# PPM2DSM_MINI.net
KiCad netlist of a schematic drawn in EAGLE
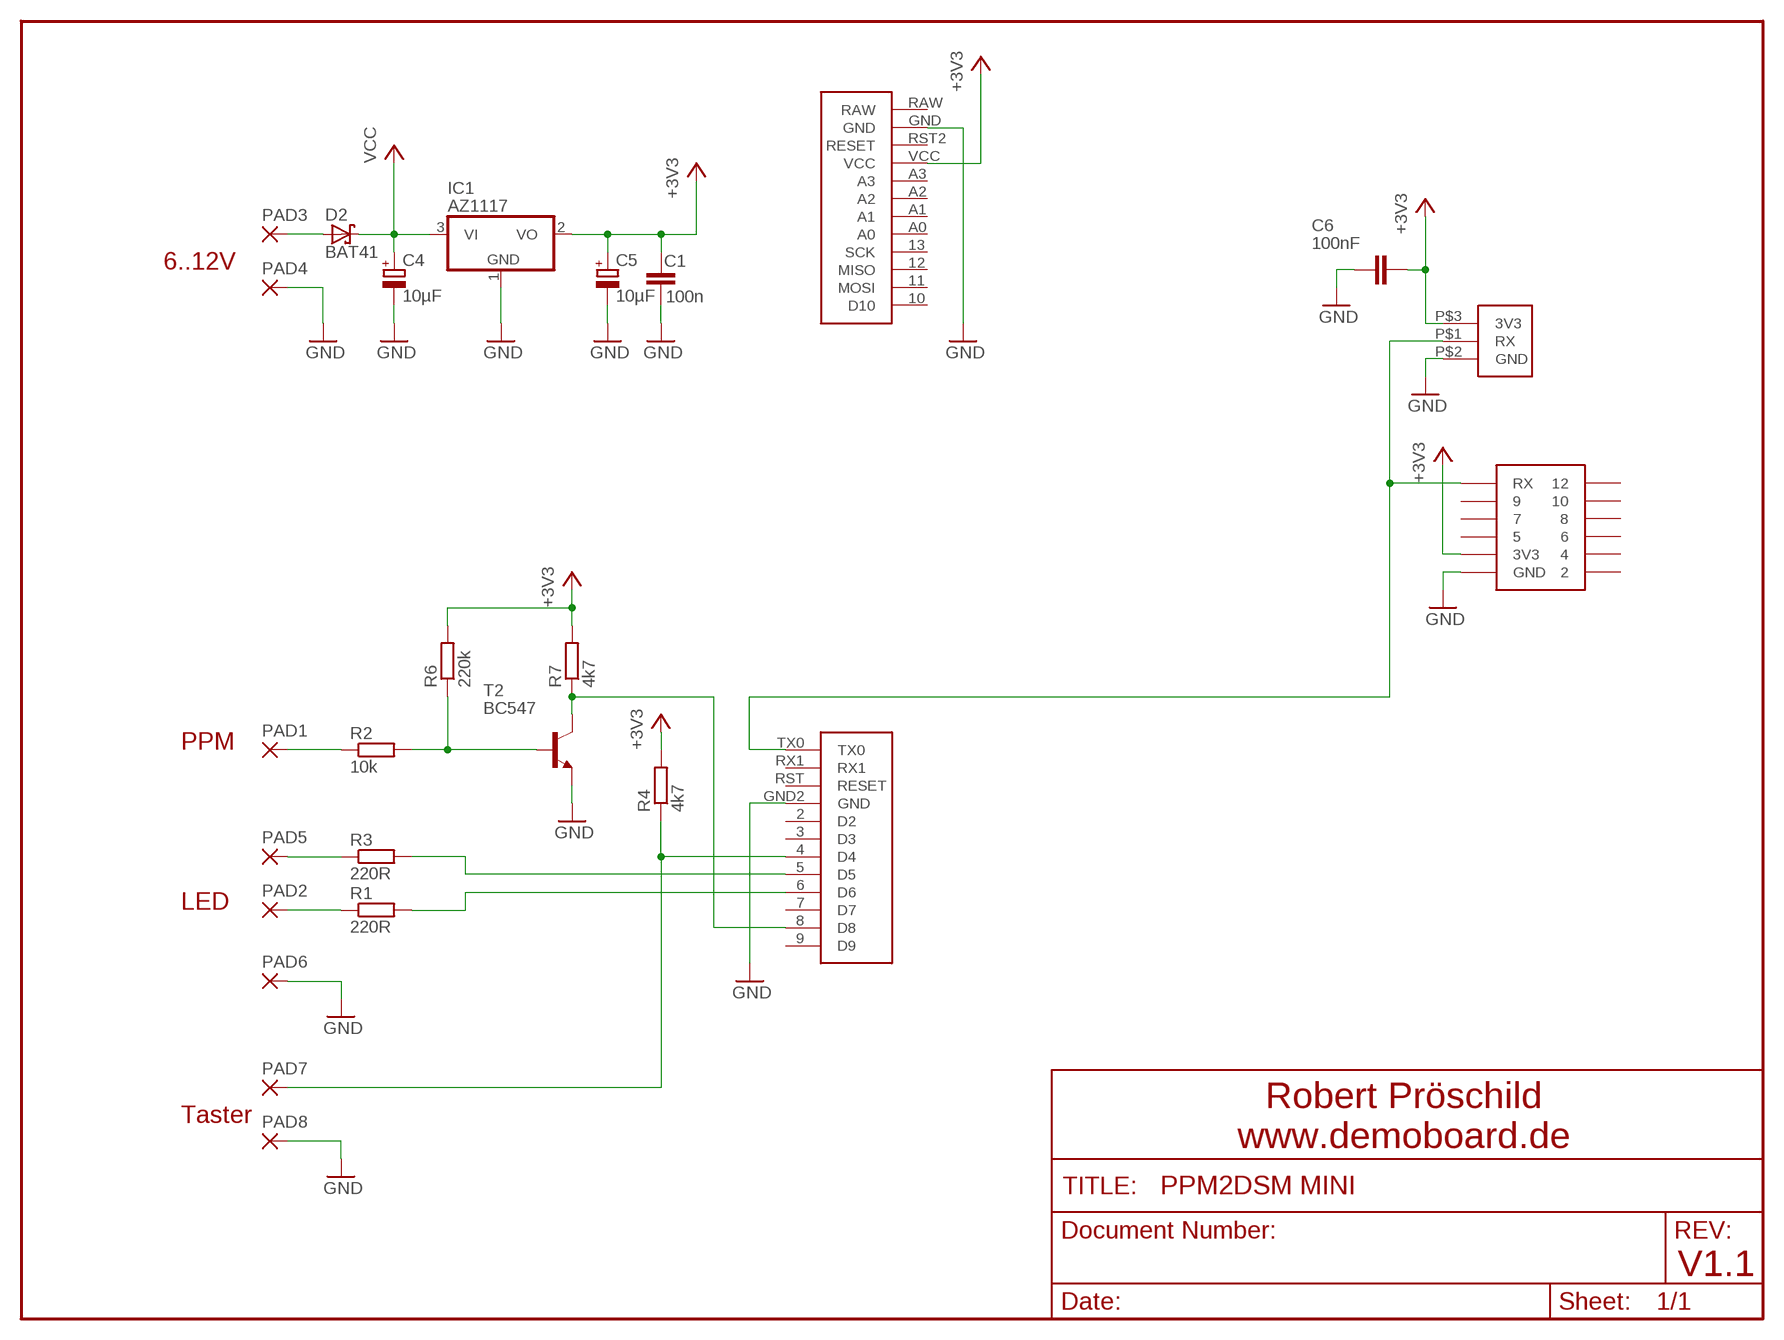
[diagram p0: schematic, sheet 1]

(export (version "E")
  (design (tool "Eeschema 10.0.6"))
  (components
    (comp (ref "C1")
      (value "100n")
      (footprint "eagle-import:C025-024X044")
      (libsource (lib "eagle-import") (part "C-EU025-024X044"))
    )
    (comp (ref "C4")
      (value "10µF")
      (footprint "eagle-import:TT2D4")
      (libsource (lib "eagle-import") (part "CPOL-EUTT2D4"))
    )
    (comp (ref "C5")
      (value "10µF")
      (footprint "eagle-import:TT2D4")
      (libsource (lib "eagle-import") (part "CPOL-EUTT2D4"))
    )
    (comp (ref "C6")
      (value "100nF")
      (footprint "eagle-import:C025-024X044")
      (libsource (lib "eagle-import") (part "C-EU025-024X044"))
    )
    (comp (ref "D2")
      (value "BAT41")
      (footprint "eagle-import:DO35-7")
      (libsource (lib "eagle-import") (part "SCHOTTKY-DIODEDO35-7"))
    )
    (comp (ref "IC1")
      (value "AZ1117")
      (footprint "eagle-import:SOT223")
      (libsource (lib "eagle-import") (part "AZ1117"))
    )
    (comp (ref "IC2")
      (value "X10EMTX")
      (footprint "eagle-import:X10EMTX")
      (libsource (lib "eagle-import") (part "X10EMTX"))
    )
    (comp (ref "IC3")
      (value "MINI_PRO")
      (footprint "eagle-import:PRO-MINI")
      (libsource (lib "eagle-import") (part "MINI_PRO"))
    )
    (comp (ref "IC4")
      (value "X1TX0")
      (footprint "eagle-import:X1TX0")
      (libsource (lib "eagle-import") (part "X1TX0"))
    )
    (comp (ref "PAD1")
      (value "SMD5")
      (footprint "eagle-import:SMD2,54-5,08")
      (libsource (lib "eagle-import") (part "SMD5"))
    )
    (comp (ref "PAD2")
      (value "SMD5")
      (footprint "eagle-import:SMD2,54-5,08")
      (libsource (lib "eagle-import") (part "SMD5"))
    )
    (comp (ref "PAD3")
      (value "SMD5")
      (footprint "eagle-import:SMD2,54-5,08")
      (libsource (lib "eagle-import") (part "SMD5"))
    )
    (comp (ref "PAD4")
      (value "SMD5")
      (footprint "eagle-import:SMD2,54-5,08")
      (libsource (lib "eagle-import") (part "SMD5"))
    )
    (comp (ref "PAD5")
      (value "SMD5")
      (footprint "eagle-import:SMD2,54-5,08")
      (libsource (lib "eagle-import") (part "SMD5"))
    )
    (comp (ref "PAD6")
      (value "SMD5")
      (footprint "eagle-import:SMD2,54-5,08")
      (libsource (lib "eagle-import") (part "SMD5"))
    )
    (comp (ref "PAD7")
      (value "SMD5")
      (footprint "eagle-import:SMD2,54-5,08")
      (libsource (lib "eagle-import") (part "SMD5"))
    )
    (comp (ref "PAD8")
      (value "SMD5")
      (footprint "eagle-import:SMD2,54-5,08")
      (libsource (lib "eagle-import") (part "SMD5"))
    )
    (comp (ref "R1")
      (value "220R")
      (footprint "eagle-import:0204_5")
      (libsource (lib "eagle-import") (part "R-EU_0204/5"))
    )
    (comp (ref "R2")
      (value "10k")
      (footprint "eagle-import:0204_5")
      (libsource (lib "eagle-import") (part "R-EU_0204/5"))
    )
    (comp (ref "R3")
      (value "220R")
      (footprint "eagle-import:0204_5")
      (libsource (lib "eagle-import") (part "R-EU_0204/5"))
    )
    (comp (ref "R4")
      (value "4k7")
      (footprint "eagle-import:0204_5")
      (libsource (lib "eagle-import") (part "R-EU_0204/5"))
    )
    (comp (ref "R6")
      (value "220k")
      (footprint "eagle-import:0204_5")
      (libsource (lib "eagle-import") (part "R-EU_0204/5"))
    )
    (comp (ref "R7")
      (value "4k7")
      (footprint "eagle-import:0204_5")
      (libsource (lib "eagle-import") (part "R-EU_0204/5"))
    )
    (comp (ref "T2")
      (value "BC547")
      (footprint "eagle-import:TO92")
      (libsource (lib "eagle-import") (part "BC547"))
    )
  )
  (nets
    (net (code "1") (name "+3V3") (class "Default")
      (node (ref "C1") (pin "2") (pinfunction "2_2") (pintype "passive"))
      (node (ref "C5") (pin "+") (pinfunction "+_+") (pintype "passive"))
      (node (ref "C6") (pin "2") (pinfunction "2_2") (pintype "passive"))
      (node (ref "IC1") (pin "2") (pinfunction "VO_2") (pintype "passive"))
      (node (ref "IC2") (pin "P$3") (pinfunction "3V3_P$3") (pintype "power_in"))
      (node (ref "IC3") (pin "VCC") (pinfunction "VCC_VCC") (pintype "power_in"))
      (node (ref "IC4") (pin "3") (pinfunction "3V3_3") (pintype "bidirectional"))
      (node (ref "R4") (pin "2") (pinfunction "2_2") (pintype "passive"))
      (node (ref "R6") (pin "2") (pinfunction "2_2") (pintype "passive"))
      (node (ref "R7") (pin "2") (pinfunction "2_2") (pintype "passive"))
    )
    (net (code "2") (name "/2") (class "Default")
      (node (ref "IC4") (pin "2") (pinfunction "2_2") (pintype "power_in"))
    )
    (net (code "3") (name "/4") (class "Default")
      (node (ref "IC4") (pin "4") (pinfunction "4_4") (pintype "power_in"))
    )
    (net (code "4") (name "/RAW") (class "Default")
      (node (ref "IC3") (pin "RAW") (pinfunction "RAW_RAW") (pintype "power_in"))
    )
    (net (code "5") (name "GND") (class "Default")
      (node (ref "C1") (pin "1") (pinfunction "1_1") (pintype "passive"))
      (node (ref "C4") (pin "-") (pinfunction "-_-") (pintype "passive"))
      (node (ref "C5") (pin "-") (pinfunction "-_-") (pintype "passive"))
      (node (ref "C6") (pin "1") (pinfunction "1_1") (pintype "passive"))
      (node (ref "IC1") (pin "1") (pinfunction "GND_1") (pintype "passive"))
      (node (ref "IC2") (pin "P$2") (pinfunction "GND_P$2") (pintype "power_in"))
      (node (ref "IC3") (pin "GND") (pinfunction "GND_GND") (pintype "power_in"))
      (node (ref "IC3") (pin "GND2") (pinfunction "GND_GND2") (pintype "power_in"))
      (node (ref "IC4") (pin "1") (pinfunction "GND_1") (pintype "bidirectional"))
      (node (ref "PAD4") (pin "1") (pinfunction "P_1") (pintype "passive"))
      (node (ref "PAD6") (pin "1") (pinfunction "P_1") (pintype "passive"))
      (node (ref "PAD8") (pin "1") (pinfunction "P_1") (pintype "passive"))
      (node (ref "T2") (pin "1") (pinfunction "E_1") (pintype "passive"))
    )
    (net (code "6") (name "Net-(IC2-RX)") (class "Default")
      (node (ref "IC2") (pin "P$1") (pinfunction "RX_P$1") (pintype "input"))
      (node (ref "IC3") (pin "TX0") (pinfunction "TX0_TX0") (pintype "bidirectional"))
      (node (ref "IC4") (pin "11") (pinfunction "RX_11") (pintype "bidirectional"))
    )
    (net (code "7") (name "Net-(IC3B-D4)") (class "Default")
      (node (ref "IC3") (pin "4") (pinfunction "D4_4") (pintype "bidirectional"))
      (node (ref "PAD7") (pin "1") (pinfunction "P_1") (pintype "passive"))
      (node (ref "R4") (pin "1") (pinfunction "1_1") (pintype "passive"))
    )
    (net (code "8") (name "Net-(IC3B-D5)") (class "Default")
      (node (ref "IC3") (pin "5") (pinfunction "D5_5") (pintype "bidirectional"))
      (node (ref "R3") (pin "2") (pinfunction "2_2") (pintype "passive"))
    )
    (net (code "9") (name "Net-(IC3B-D6)") (class "Default")
      (node (ref "IC3") (pin "6") (pinfunction "D6_6") (pintype "bidirectional"))
      (node (ref "R1") (pin "2") (pinfunction "2_2") (pintype "passive"))
    )
    (net (code "10") (name "Net-(IC3B-D8)") (class "Default")
      (node (ref "IC3") (pin "8") (pinfunction "D8_8") (pintype "bidirectional"))
      (node (ref "R7") (pin "1") (pinfunction "1_1") (pintype "passive"))
      (node (ref "T2") (pin "3") (pinfunction "C_3") (pintype "passive"))
    )
    (net (code "11") (name "Net-(PAD1-P)") (class "Default")
      (node (ref "PAD1") (pin "1") (pinfunction "P_1") (pintype "passive"))
      (node (ref "R2") (pin "1") (pinfunction "1_1") (pintype "passive"))
    )
    (net (code "12") (name "Net-(PAD2-P)") (class "Default")
      (node (ref "PAD2") (pin "1") (pinfunction "P_1") (pintype "passive"))
      (node (ref "R1") (pin "1") (pinfunction "1_1") (pintype "passive"))
    )
    (net (code "13") (name "Net-(PAD3-P)") (class "Default")
      (node (ref "D2") (pin "A") (pinfunction "A_A") (pintype "passive"))
      (node (ref "PAD3") (pin "1") (pinfunction "P_1") (pintype "passive"))
    )
    (net (code "14") (name "Net-(PAD5-P)") (class "Default")
      (node (ref "PAD5") (pin "1") (pinfunction "P_1") (pintype "passive"))
      (node (ref "R3") (pin "1") (pinfunction "1_1") (pintype "passive"))
    )
    (net (code "15") (name "Net-(T2-B)") (class "Default")
      (node (ref "R2") (pin "2") (pinfunction "2_2") (pintype "passive"))
      (node (ref "R6") (pin "1") (pinfunction "1_1") (pintype "passive"))
      (node (ref "T2") (pin "2") (pinfunction "B_2") (pintype "passive"))
    )
    (net (code "16") (name "VCC") (class "Default")
      (node (ref "C4") (pin "+") (pinfunction "+_+") (pintype "passive"))
      (node (ref "D2") (pin "C") (pinfunction "C_C") (pintype "passive"))
      (node (ref "IC1") (pin "3") (pinfunction "VI_3") (pintype "input"))
    )
    (net (code "17") (name "unconnected-(IC3-PadA0)") (class "Default")
      (node (ref "IC3") (pin "A0") (pinfunction "A0_A0") (pintype "bidirectional"))
    )
    (net (code "18") (name "unconnected-(IC3-PadA1)") (class "Default")
      (node (ref "IC3") (pin "A1") (pinfunction "A1_A1") (pintype "bidirectional"))
    )
    (net (code "19") (name "unconnected-(IC3-PadA2)") (class "Default")
      (node (ref "IC3") (pin "A2") (pinfunction "A2_A2") (pintype "bidirectional"))
    )
    (net (code "20") (name "unconnected-(IC3-PadA3)") (class "Default")
      (node (ref "IC3") (pin "A3") (pinfunction "A3_A3") (pintype "bidirectional"))
    )
    (net (code "21") (name "unconnected-(IC3-PadRX1)") (class "Default")
      (node (ref "IC3") (pin "RX1") (pinfunction "RX1_RX1") (pintype "bidirectional"))
    )
    (net (code "22") (name "unconnected-(IC3A-D10-Pad10)") (class "Default")
      (node (ref "IC3") (pin "10") (pinfunction "D10_10") (pintype "bidirectional"))
    )
    (net (code "23") (name "unconnected-(IC3A-MISO-Pad12)") (class "Default")
      (node (ref "IC3") (pin "12") (pinfunction "MISO_12") (pintype "bidirectional"))
    )
    (net (code "24") (name "unconnected-(IC3A-MOSI-Pad11)") (class "Default")
      (node (ref "IC3") (pin "11") (pinfunction "MOSI_11") (pintype "bidirectional"))
    )
    (net (code "25") (name "unconnected-(IC3A-RESET-PadRST2)") (class "Default")
      (node (ref "IC3") (pin "RST2") (pinfunction "RESET_RST2") (pintype "bidirectional"))
    )
    (net (code "26") (name "unconnected-(IC3A-SCK-Pad13)") (class "Default")
      (node (ref "IC3") (pin "13") (pinfunction "SCK_13") (pintype "bidirectional"))
    )
    (net (code "27") (name "unconnected-(IC3B-D2-Pad2)") (class "Default")
      (node (ref "IC3") (pin "2") (pinfunction "D2_2") (pintype "bidirectional"))
    )
    (net (code "28") (name "unconnected-(IC3B-D3-Pad3)") (class "Default")
      (node (ref "IC3") (pin "3") (pinfunction "D3_3") (pintype "bidirectional"))
    )
    (net (code "29") (name "unconnected-(IC3B-D7-Pad7)") (class "Default")
      (node (ref "IC3") (pin "7") (pinfunction "D7_7") (pintype "bidirectional"))
    )
    (net (code "30") (name "unconnected-(IC3B-D9-Pad9)") (class "Default")
      (node (ref "IC3") (pin "9") (pinfunction "D9_9") (pintype "bidirectional"))
    )
    (net (code "31") (name "unconnected-(IC3B-RESET-PadRST)") (class "Default")
      (node (ref "IC3") (pin "RST") (pinfunction "RESET_RST") (pintype "bidirectional"))
    )
    (net (code "32") (name "unconnected-(IC4-Pad5)") (class "Default")
      (node (ref "IC4") (pin "5") (pinfunction "5_5") (pintype "bidirectional"))
    )
    (net (code "33") (name "unconnected-(IC4-Pad6)") (class "Default")
      (node (ref "IC4") (pin "6") (pinfunction "6_6") (pintype "bidirectional"))
    )
    (net (code "34") (name "unconnected-(IC4-Pad7)") (class "Default")
      (node (ref "IC4") (pin "7") (pinfunction "7_7") (pintype "bidirectional"))
    )
    (net (code "35") (name "unconnected-(IC4-Pad8)") (class "Default")
      (node (ref "IC4") (pin "8") (pinfunction "8_8") (pintype "bidirectional"))
    )
    (net (code "36") (name "unconnected-(IC4-Pad9)") (class "Default")
      (node (ref "IC4") (pin "9") (pinfunction "9_9") (pintype "bidirectional"))
    )
    (net (code "37") (name "unconnected-(IC4-Pad10)") (class "Default")
      (node (ref "IC4") (pin "10") (pinfunction "10_10") (pintype "bidirectional"))
    )
    (net (code "38") (name "unconnected-(IC4-Pad12)") (class "Default")
      (node (ref "IC4") (pin "12") (pinfunction "12_12") (pintype "input"))
    )
  )
)
